# Grove_-_EL_Driver_v1_0.net
KiCad netlist of a schematic drawn in EAGLE
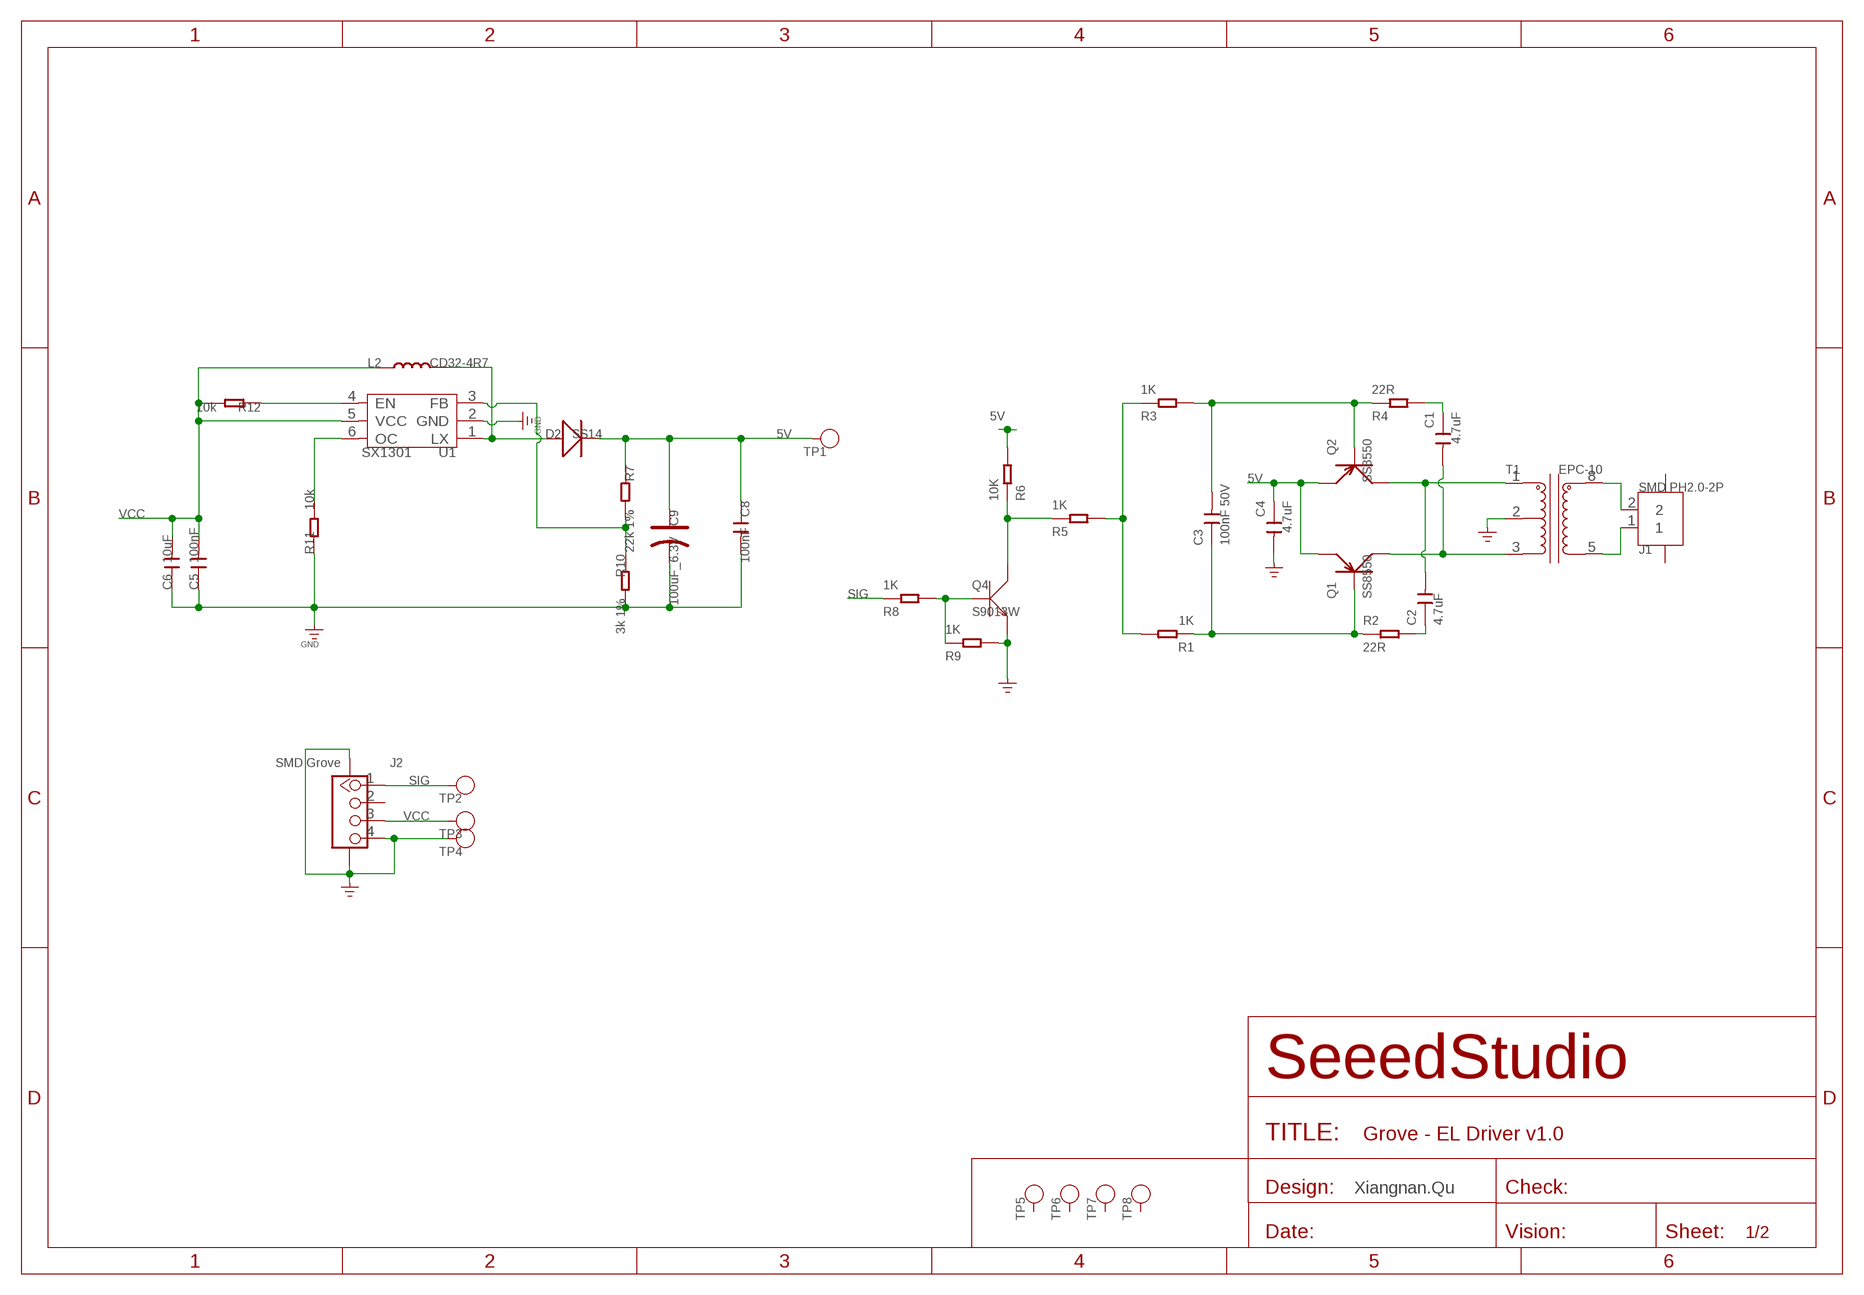
[diagram p0: schematic, sheet 1]
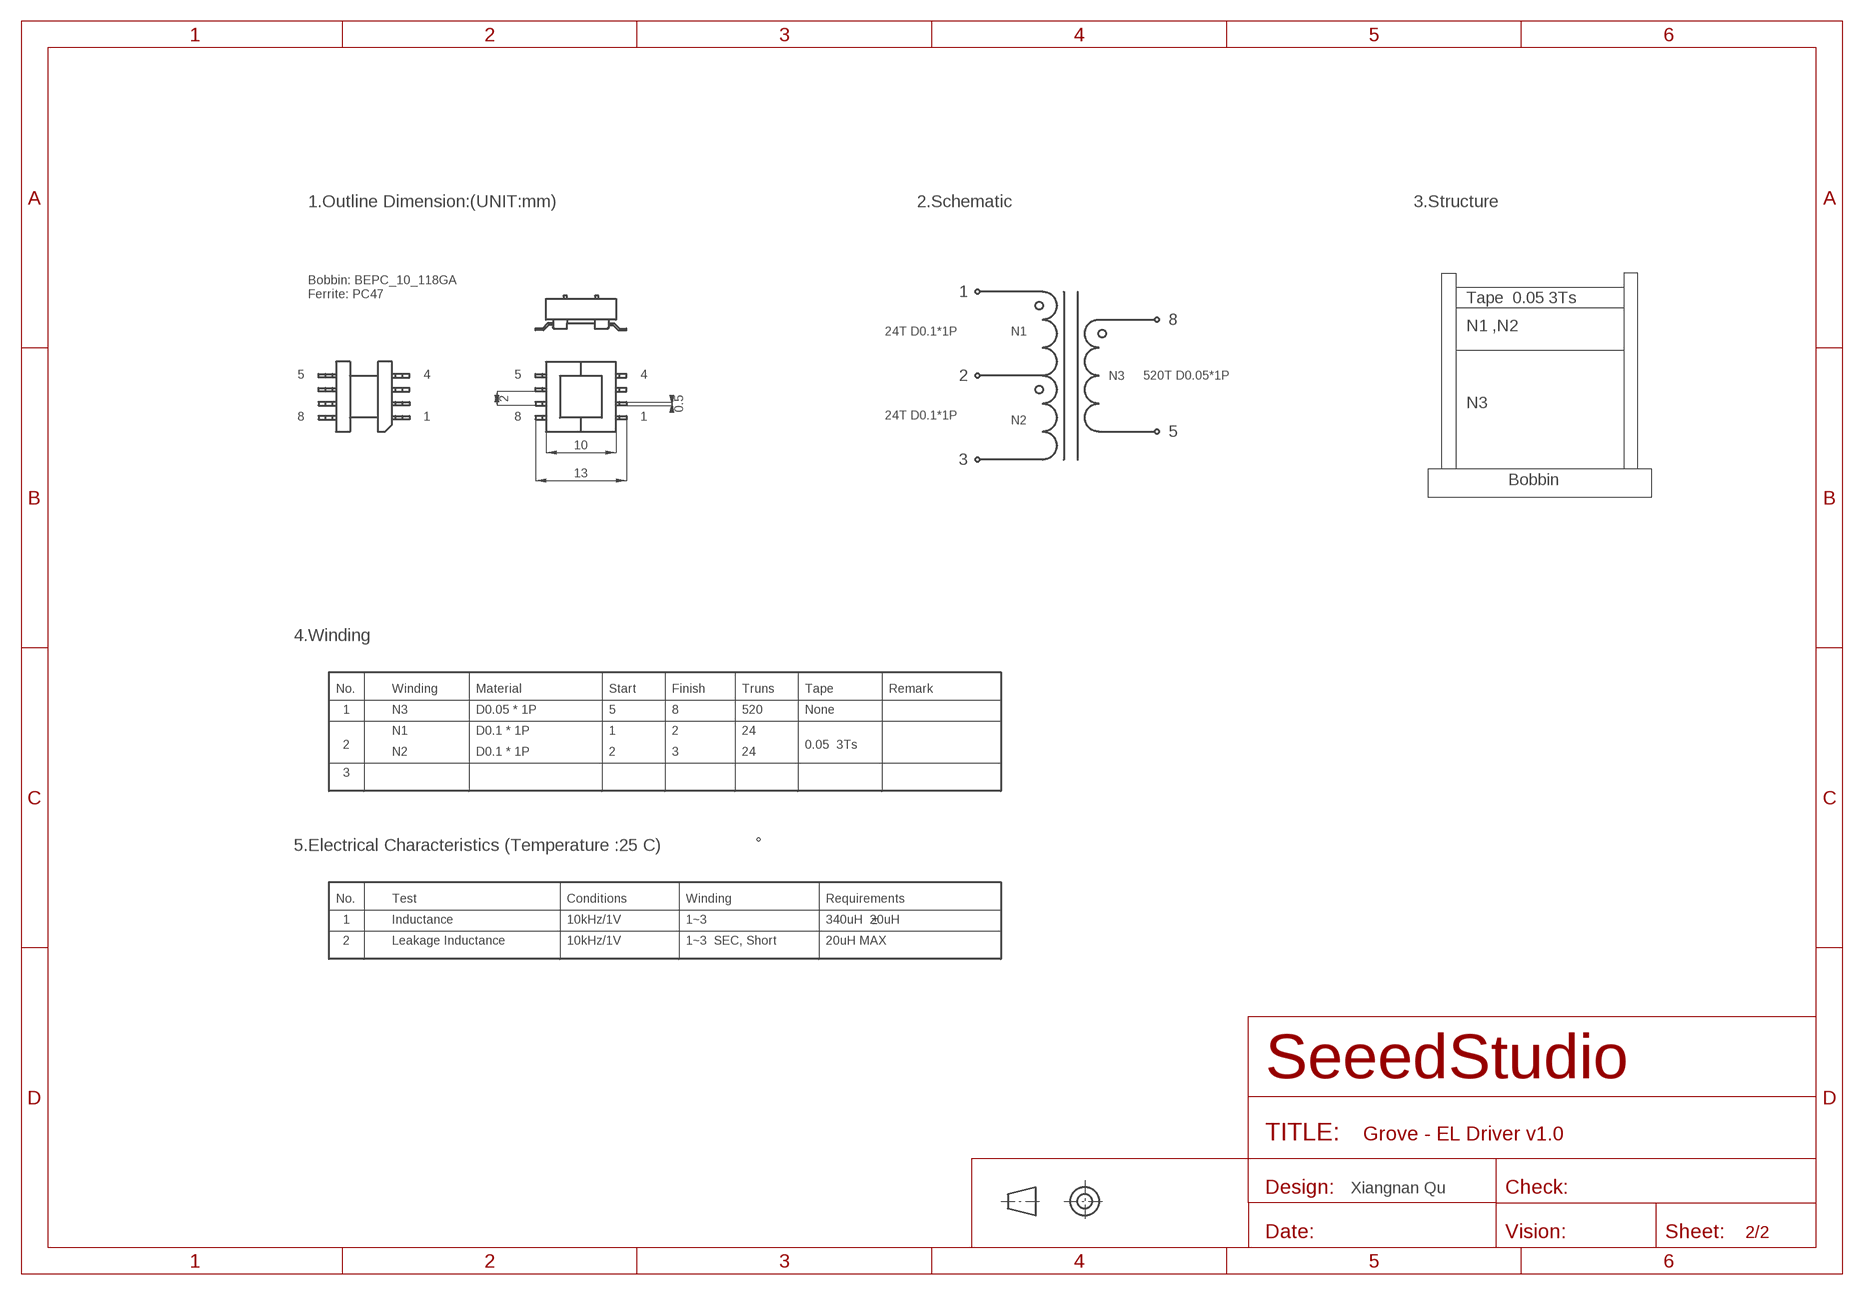
[diagram p1: schematic, sheet 2]

(export (version "E")
  (design (tool "Eeschema 10.0.6"))
  (components
    (comp (ref "C1")
      (value "4.7uF")
      (footprint "eagle-import:C0805")
      (libsource (lib "eagle-import") (part "CAP-0805"))
    )
    (comp (ref "C2")
      (value "4.7uF")
      (footprint "eagle-import:C0805")
      (libsource (lib "eagle-import") (part "CAP-0805"))
    )
    (comp (ref "C3")
      (value "100nF 50V")
      (footprint "eagle-import:C0603")
      (libsource (lib "eagle-import") (part "CAP-0603"))
    )
    (comp (ref "C4")
      (value "4.7uF")
      (footprint "eagle-import:C0805")
      (libsource (lib "eagle-import") (part "CAP-0805"))
    )
    (comp (ref "C5")
      (value "100nF")
      (footprint "eagle-import:C0603")
      (libsource (lib "eagle-import") (part "C-0603"))
    )
    (comp (ref "C6")
      (value "10uF")
      (footprint "eagle-import:C0805")
      (libsource (lib "eagle-import") (part "C-0805"))
    )
    (comp (ref "C8")
      (value "100nF")
      (footprint "eagle-import:C0603")
      (libsource (lib "eagle-import") (part "C-0603"))
    )
    (comp (ref "C9")
      (value "100uF_6.3V")
      (footprint "eagle-import:AVX-B")
      (libsource (lib "eagle-import") (part "CAP-AVX-B"))
    )
    (comp (ref "D2")
      (value "SS14")
      (footprint "eagle-import:DO-214AC")
      (libsource (lib "eagle-import") (part "D'SMA'"))
    )
    (comp (ref "J1")
      (value "SMD PH2.0-2P")
      (footprint "eagle-import:SMD-PH2.0-2P")
      (libsource (lib "eagle-import") (part "PH2.0-2P"))
    )
    (comp (ref "J2")
      (value "SMD Grove")
      (footprint "eagle-import:4P-SMD-2.0")
      (libsource (lib "eagle-import") (part "GROVE-CONNECTOR-SMD'DD'"))
    )
    (comp (ref "L2")
      (value "CD32-4R7")
      (footprint "eagle-import:SD32-4R7MC")
      (libsource (lib "eagle-import") (part "CD32'4R7'"))
    )
    (comp (ref "Q1")
      (value "SS8550")
      (footprint "eagle-import:SOT-23")
      (libsource (lib "eagle-import") (part "TRANSISTOR-PNP-SOT23"))
    )
    (comp (ref "Q2")
      (value "SS8550")
      (footprint "eagle-import:SOT-23")
      (libsource (lib "eagle-import") (part "TRANSISTOR-PNP-SOT23"))
    )
    (comp (ref "Q4")
      (value "S9013W")
      (footprint "eagle-import:SOT-323")
      (libsource (lib "eagle-import") (part "TRANSISTOR-NPN-SOT323"))
    )
    (comp (ref "R1")
      (value "1K")
      (footprint "eagle-import:R0603")
      (libsource (lib "eagle-import") (part "RES-0603"))
    )
    (comp (ref "R2")
      (value "22R")
      (footprint "eagle-import:R0603")
      (libsource (lib "eagle-import") (part "RES-0603"))
    )
    (comp (ref "R3")
      (value "1K")
      (footprint "eagle-import:R0603")
      (libsource (lib "eagle-import") (part "RES-0603"))
    )
    (comp (ref "R4")
      (value "22R")
      (footprint "eagle-import:R0603")
      (libsource (lib "eagle-import") (part "RES-0603"))
    )
    (comp (ref "R5")
      (value "1K")
      (footprint "eagle-import:R0603")
      (libsource (lib "eagle-import") (part "RES-0603"))
    )
    (comp (ref "R6")
      (value "10K")
      (footprint "eagle-import:R0603")
      (libsource (lib "eagle-import") (part "RES-0603"))
    )
    (comp (ref "R7")
      (value "22k 1%")
      (footprint "eagle-import:R0603")
      (libsource (lib "eagle-import") (part "R-0603"))
    )
    (comp (ref "R8")
      (value "1K")
      (footprint "eagle-import:R0603")
      (libsource (lib "eagle-import") (part "RES-0603"))
    )
    (comp (ref "R9")
      (value "1K")
      (footprint "eagle-import:R0603")
      (libsource (lib "eagle-import") (part "RES-0603"))
    )
    (comp (ref "R10")
      (value "3k 1%")
      (footprint "eagle-import:R0603")
      (libsource (lib "eagle-import") (part "R-0603"))
    )
    (comp (ref "R11")
      (value "10k")
      (footprint "eagle-import:R0603")
      (libsource (lib "eagle-import") (part "R-0603"))
    )
    (comp (ref "R12")
      (value "10k")
      (footprint "eagle-import:R0603")
      (libsource (lib "eagle-import") (part "R-0603"))
    )
    (comp (ref "T1")
      (value "EPC-10")
      (footprint "eagle-import:EPC-1003-4+4PIN")
      (libsource (lib "eagle-import") (part "TRANSFORMER"))
    )
    (comp (ref "TP1")
      (value "PAD-TEST-POINT'4545'")
      (footprint "eagle-import:TP-D45MIL")
      (fields (field (name "PARTNO") "DNP"))
      (libsource (lib "eagle-import") (part "PAD-TEST-POINT'4545'"))
    )
    (comp (ref "TP2")
      (value "PAD-TEST-POINT'4545'")
      (footprint "eagle-import:TP-D45MIL")
      (fields (field (name "PARTNO") "DNP"))
      (libsource (lib "eagle-import") (part "PAD-TEST-POINT'4545'"))
    )
    (comp (ref "TP3")
      (value "PAD-TEST-POINT'4545'")
      (footprint "eagle-import:TP-D45MIL")
      (fields (field (name "PARTNO") "DNP"))
      (libsource (lib "eagle-import") (part "PAD-TEST-POINT'4545'"))
    )
    (comp (ref "TP4")
      (value "PAD-TEST-POINT'4545'")
      (footprint "eagle-import:TP-D45MIL")
      (fields (field (name "PARTNO") "DNP"))
      (libsource (lib "eagle-import") (part "PAD-TEST-POINT'4545'"))
    )
    (comp (ref "TP5")
      (value "PAD-TEST-POINT'4545'")
      (footprint "eagle-import:TP-D45MIL")
      (fields (field (name "PARTNO") "DNP"))
      (libsource (lib "eagle-import") (part "PAD-TEST-POINT'4545'"))
    )
    (comp (ref "TP6")
      (value "PAD-TEST-POINT'4545'")
      (footprint "eagle-import:TP-D45MIL")
      (fields (field (name "PARTNO") "DNP"))
      (libsource (lib "eagle-import") (part "PAD-TEST-POINT'4545'"))
    )
    (comp (ref "TP7")
      (value "PAD-TEST-POINT'4545'")
      (footprint "eagle-import:TP-D45MIL")
      (fields (field (name "PARTNO") "DNP"))
      (libsource (lib "eagle-import") (part "PAD-TEST-POINT'4545'"))
    )
    (comp (ref "TP8")
      (value "PAD-TEST-POINT'4545'")
      (footprint "eagle-import:TP-D45MIL")
      (fields (field (name "PARTNO") "DNP"))
      (libsource (lib "eagle-import") (part "PAD-TEST-POINT'4545'"))
    )
    (comp (ref "U1")
      (value "SX1301")
      (footprint "eagle-import:SOT23-6L")
      (libsource (lib "eagle-import") (part "SX1301"))
    )
  )
  (nets
    (net (code "1") (name "5V") (class "Default")
      (node (ref "C4") (pin "1") (pinfunction "1_1") (pintype "passive"))
      (node (ref "C8") (pin "1") (pinfunction "1_1") (pintype "passive"))
      (node (ref "C9") (pin "+") (pinfunction "+_+") (pintype "passive"))
      (node (ref "D2") (pin "2") (pinfunction "-_2") (pintype "passive"))
      (node (ref "Q1") (pin "2") (pinfunction "E_2") (pintype "passive"))
      (node (ref "Q2") (pin "2") (pinfunction "E_2") (pintype "passive"))
      (node (ref "R6") (pin "2") (pinfunction "2_2") (pintype "passive"))
      (node (ref "R7") (pin "1") (pinfunction "1_1") (pintype "passive"))
      (node (ref "TP1") (pin "T") (pinfunction "T_T") (pintype "bidirectional"))
    )
    (net (code "2") (name "GND") (class "Default")
      (node (ref "C4") (pin "2") (pinfunction "2_2") (pintype "passive"))
      (node (ref "C5") (pin "1") (pinfunction "1_1") (pintype "passive"))
      (node (ref "C6") (pin "1") (pinfunction "1_1") (pintype "passive"))
      (node (ref "C8") (pin "2") (pinfunction "2_2") (pintype "passive"))
      (node (ref "C9") (pin "-") (pinfunction "-_-") (pintype "passive"))
      (node (ref "J2") (pin "4") (pinfunction "4_4") (pintype "bidirectional"))
      (node (ref "J2") (pin "SS1") (pinfunction "SS1_SS1") (pintype "bidirectional"))
      (node (ref "J2") (pin "SS2") (pinfunction "SS2_SS2") (pintype "bidirectional"))
      (node (ref "Q4") (pin "2") (pinfunction "E_2") (pintype "passive"))
      (node (ref "R10") (pin "2") (pinfunction "2_2") (pintype "passive"))
      (node (ref "R11") (pin "1") (pinfunction "1_1") (pintype "passive"))
      (node (ref "R9") (pin "2") (pinfunction "2_2") (pintype "passive"))
      (node (ref "T1") (pin "2") (pinfunction "P$2_2") (pintype "bidirectional"))
      (node (ref "TP4") (pin "T") (pinfunction "T_T") (pintype "bidirectional"))
      (node (ref "U1") (pin "2") (pinfunction "GND_2") (pintype "bidirectional"))
    )
    (net (code "3") (name "Net-(C1-Pad1)") (class "Default")
      (node (ref "C1") (pin "1") (pinfunction "1_1") (pintype "passive"))
      (node (ref "R4") (pin "2") (pinfunction "2_2") (pintype "passive"))
    )
    (net (code "4") (name "Net-(C2-Pad1)") (class "Default")
      (node (ref "C2") (pin "1") (pinfunction "1_1") (pintype "passive"))
      (node (ref "R2") (pin "2") (pinfunction "2_2") (pintype "passive"))
    )
    (net (code "5") (name "Net-(D2-+)") (class "Default")
      (node (ref "D2") (pin "1") (pinfunction "+_1") (pintype "passive"))
      (node (ref "L2") (pin "2") (pinfunction "2_2") (pintype "passive"))
      (node (ref "U1") (pin "1") (pinfunction "LX_1") (pintype "bidirectional"))
    )
    (net (code "6") (name "Net-(Q1-B)") (class "Default")
      (node (ref "C3") (pin "1") (pinfunction "1_1") (pintype "passive"))
      (node (ref "Q1") (pin "1") (pinfunction "B_1") (pintype "passive"))
      (node (ref "R1") (pin "1") (pinfunction "1_1") (pintype "passive"))
      (node (ref "R2") (pin "1") (pinfunction "1_1") (pintype "passive"))
    )
    (net (code "7") (name "Net-(Q1-C)") (class "Default")
      (node (ref "C1") (pin "2") (pinfunction "2_2") (pintype "passive"))
      (node (ref "Q1") (pin "3") (pinfunction "C_3") (pintype "passive"))
      (node (ref "T1") (pin "3") (pinfunction "P$3_3") (pintype "bidirectional"))
    )
    (net (code "8") (name "Net-(Q2-B)") (class "Default")
      (node (ref "C3") (pin "2") (pinfunction "2_2") (pintype "passive"))
      (node (ref "Q2") (pin "1") (pinfunction "B_1") (pintype "passive"))
      (node (ref "R3") (pin "2") (pinfunction "2_2") (pintype "passive"))
      (node (ref "R4") (pin "1") (pinfunction "1_1") (pintype "passive"))
    )
    (net (code "9") (name "Net-(Q2-C)") (class "Default")
      (node (ref "C2") (pin "2") (pinfunction "2_2") (pintype "passive"))
      (node (ref "Q2") (pin "3") (pinfunction "C_3") (pintype "passive"))
      (node (ref "T1") (pin "1") (pinfunction "P$1_1") (pintype "bidirectional"))
    )
    (net (code "10") (name "Net-(Q4-B)") (class "Default")
      (node (ref "Q4") (pin "1") (pinfunction "B_1") (pintype "passive"))
      (node (ref "R8") (pin "2") (pinfunction "2_2") (pintype "passive"))
      (node (ref "R9") (pin "1") (pinfunction "1_1") (pintype "passive"))
    )
    (net (code "11") (name "Net-(Q4-C)") (class "Default")
      (node (ref "Q4") (pin "3") (pinfunction "C_3") (pintype "passive"))
      (node (ref "R5") (pin "1") (pinfunction "1_1") (pintype "passive"))
      (node (ref "R6") (pin "1") (pinfunction "1_1") (pintype "passive"))
    )
    (net (code "12") (name "Net-(R1-Pad2)") (class "Default")
      (node (ref "R1") (pin "2") (pinfunction "2_2") (pintype "passive"))
      (node (ref "R3") (pin "1") (pinfunction "1_1") (pintype "passive"))
      (node (ref "R5") (pin "2") (pinfunction "2_2") (pintype "passive"))
    )
    (net (code "13") (name "Net-(T1-P$4)") (class "Default")
      (node (ref "J1") (pin "1") (pinfunction "1_1") (pintype "bidirectional"))
      (node (ref "T1") (pin "5") (pinfunction "P$4_5") (pintype "bidirectional"))
    )
    (net (code "14") (name "Net-(T1-P$5)") (class "Default")
      (node (ref "J1") (pin "2") (pinfunction "2_2") (pintype "bidirectional"))
      (node (ref "T1") (pin "8") (pinfunction "P$5_8") (pintype "bidirectional"))
    )
    (net (code "15") (name "Net-(U1-EN)") (class "Default")
      (node (ref "R12") (pin "1") (pinfunction "1_1") (pintype "passive"))
      (node (ref "U1") (pin "4") (pinfunction "EN_4") (pintype "bidirectional"))
    )
    (net (code "16") (name "Net-(U1-FB)") (class "Default")
      (node (ref "R10") (pin "1") (pinfunction "1_1") (pintype "passive"))
      (node (ref "R7") (pin "2") (pinfunction "2_2") (pintype "passive"))
      (node (ref "U1") (pin "3") (pinfunction "FB_3") (pintype "bidirectional"))
    )
    (net (code "17") (name "Net-(U1-OC)") (class "Default")
      (node (ref "R11") (pin "2") (pinfunction "2_2") (pintype "passive"))
      (node (ref "U1") (pin "6") (pinfunction "OC_6") (pintype "bidirectional"))
    )
    (net (code "18") (name "SIG") (class "Default")
      (node (ref "J2") (pin "1") (pinfunction "1_1") (pintype "bidirectional"))
      (node (ref "R8") (pin "1") (pinfunction "1_1") (pintype "passive"))
      (node (ref "TP2") (pin "T") (pinfunction "T_T") (pintype "bidirectional"))
    )
    (net (code "19") (name "VCC") (class "Default")
      (node (ref "C5") (pin "2") (pinfunction "2_2") (pintype "passive"))
      (node (ref "C6") (pin "2") (pinfunction "2_2") (pintype "passive"))
      (node (ref "J2") (pin "3") (pinfunction "3_3") (pintype "bidirectional"))
      (node (ref "L2") (pin "1") (pinfunction "1_1") (pintype "passive"))
      (node (ref "R12") (pin "2") (pinfunction "2_2") (pintype "passive"))
      (node (ref "TP3") (pin "T") (pinfunction "T_T") (pintype "bidirectional"))
      (node (ref "U1") (pin "5") (pinfunction "VCC_5") (pintype "bidirectional"))
    )
    (net (code "20") (name "unconnected-(J1-Pad3)") (class "Default")
      (node (ref "J1") (pin "3") (pinfunction "3_3") (pintype "bidirectional"))
    )
    (net (code "21") (name "unconnected-(J1-Pad4)") (class "Default")
      (node (ref "J1") (pin "4") (pinfunction "4_4") (pintype "bidirectional"))
    )
    (net (code "22") (name "unconnected-(J2-Pad2)") (class "Default")
      (node (ref "J2") (pin "2") (pinfunction "2_2") (pintype "bidirectional"))
    )
    (net (code "23") (name "unconnected-(TP5-PadT)") (class "Default")
      (node (ref "TP5") (pin "T") (pinfunction "T_T") (pintype "bidirectional"))
    )
    (net (code "24") (name "unconnected-(TP6-PadT)") (class "Default")
      (node (ref "TP6") (pin "T") (pinfunction "T_T") (pintype "bidirectional"))
    )
    (net (code "25") (name "unconnected-(TP7-PadT)") (class "Default")
      (node (ref "TP7") (pin "T") (pinfunction "T_T") (pintype "bidirectional"))
    )
    (net (code "26") (name "unconnected-(TP8-PadT)") (class "Default")
      (node (ref "TP8") (pin "T") (pinfunction "T_T") (pintype "bidirectional"))
    )
  )
)
